# WaterbedSlave.net
KiCad netlist of a schematic drawn in EAGLE
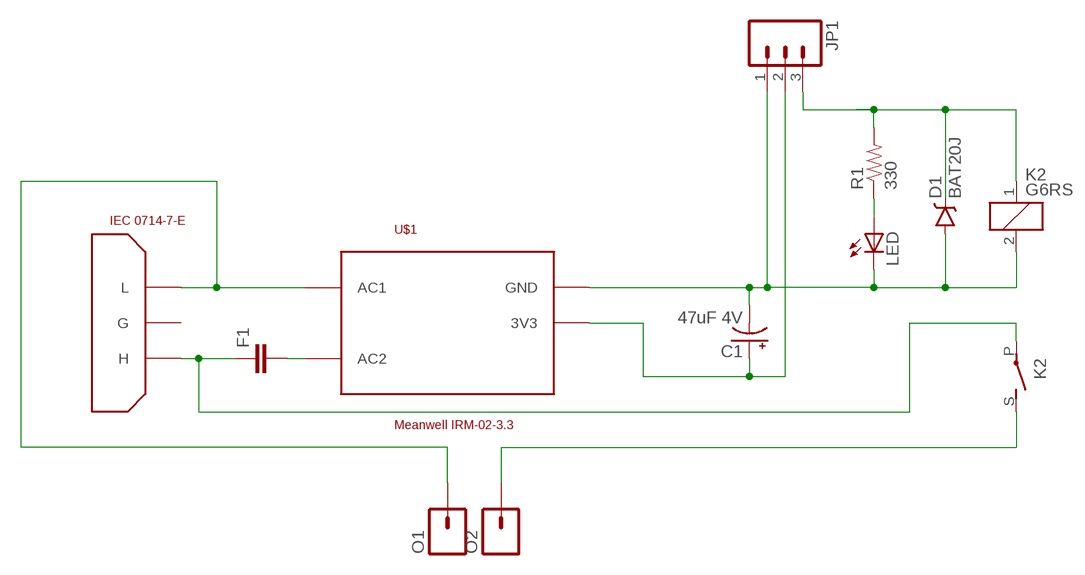
[diagram p0: schematic, sheet 1]

(export (version "E")
  (design (tool "Eeschema 10.0.6"))
  (components
    (comp (ref "C1")
      (value "47uF 4V")
      (footprint "eagle-import:CPOL-RADIAL-10UF-25V")
      (libsource (lib "eagle-import") (part "CAP_POLPTH2"))
    )
    (comp (ref "D1")
      (value "BAT20J")
      (footprint "eagle-import:SOD-323")
      (libsource (lib "eagle-import") (part "DIODE-SCHOTTKY-BAT20J"))
    )
    (comp (ref "F1")
      (value "CAPPTH1")
      (footprint "eagle-import:CAP-PTH-5MM")
      (libsource (lib "eagle-import") (part "CAPPTH1"))
    )
    (comp (ref "JP1")
      (value "M03POLAR_LOCK")
      (footprint "eagle-import:MOLEX-1X3_LOCK")
      (libsource (lib "eagle-import") (part "M03POLAR_LOCK"))
    )
    (comp (ref "K2")
      (value "G6RS")
      (footprint "eagle-import:G6RS")
      (libsource (lib "eagle-import") (part "G6RS"))
    )
    (comp (ref "LED")
      (value "LEDCHIPLED_0805")
      (footprint "eagle-import:CHIPLED_0805")
      (libsource (lib "eagle-import") (part "LEDCHIPLED_0805"))
    )
    (comp (ref "O1")
      (value "M01PTH_2MM")
      (footprint "eagle-import:1X01_2MM")
      (libsource (lib "eagle-import") (part "M01PTH_2MM"))
    )
    (comp (ref "O2")
      (value "M01PTH_2MM")
      (footprint "eagle-import:1X01_2MM")
      (libsource (lib "eagle-import") (part "M01PTH_2MM"))
    )
    (comp (ref "R1")
      (value "330")
      (footprint "eagle-import:0805")
      (libsource (lib "eagle-import") (part "RESISTOR0805-RES"))
    )
    (comp (ref "U$1")
      (value "Meanwell IRM-02-3.3")
      (footprint "eagle-import:RAC02-3.3SC")
      (libsource (lib "eagle-import") (part "RAC02-3.3SC"))
    )
    (comp (ref "U$3")
      (value "IEC 0714-7-E")
      (footprint "eagle-import:IEC")
      (libsource (lib "eagle-import") (part "IEC"))
    )
  )
  (nets
    (net (code "1") (name "Net-(C1-+)") (class "Default")
      (node (ref "C1") (pin "1") (pinfunction "+_1") (pintype "passive"))
      (node (ref "JP1") (pin "2") (pinfunction "2_2") (pintype "passive"))
      (node (ref "U$1") (pin "GND") (pinfunction "3V3_GND") (pintype "bidirectional"))
    )
    (net (code "2") (name "Net-(C1--)") (class "Default")
      (node (ref "C1") (pin "2") (pinfunction "-_2") (pintype "passive"))
      (node (ref "D1") (pin "A") (pinfunction "A_A") (pintype "passive"))
      (node (ref "JP1") (pin "1") (pinfunction "1_1") (pintype "passive"))
      (node (ref "K2") (pin "2") (pinfunction "2_2") (pintype "passive"))
      (node (ref "LED") (pin "C") (pinfunction "C_C") (pintype "passive"))
      (node (ref "U$1") (pin "3V3") (pinfunction "GND_3V3") (pintype "bidirectional"))
    )
    (net (code "3") (name "Net-(D1-PadC)") (class "Default")
      (node (ref "D1") (pin "C") (pinfunction "C_C") (pintype "passive"))
      (node (ref "JP1") (pin "3") (pinfunction "3_3") (pintype "passive"))
      (node (ref "K2") (pin "1") (pinfunction "1_1") (pintype "passive"))
      (node (ref "R1") (pin "2") (pinfunction "2_2") (pintype "passive"))
    )
    (net (code "4") (name "Net-(F1-Pad1)") (class "Default")
      (node (ref "F1") (pin "1") (pinfunction "1_1") (pintype "passive"))
      (node (ref "K2") (pin "P") (pinfunction "P_P") (pintype "passive"))
      (node (ref "U$3") (pin "H") (pinfunction "H_H") (pintype "power_in"))
    )
    (net (code "5") (name "Net-(F1-Pad2)") (class "Default")
      (node (ref "F1") (pin "2") (pinfunction "2_2") (pintype "passive"))
      (node (ref "U$1") (pin "AC2") (pinfunction "AC2_AC2") (pintype "bidirectional"))
    )
    (net (code "6") (name "Net-(K2-PadS)") (class "Default")
      (node (ref "K2") (pin "S") (pinfunction "S_S") (pintype "passive"))
      (node (ref "O2") (pin "1") (pinfunction "1_1") (pintype "passive"))
    )
    (net (code "7") (name "Net-(LED-PadA)") (class "Default")
      (node (ref "LED") (pin "A") (pinfunction "A_A") (pintype "passive"))
      (node (ref "R1") (pin "1") (pinfunction "1_1") (pintype "passive"))
    )
    (net (code "8") (name "Net-(O1-Pad1)") (class "Default")
      (node (ref "O1") (pin "1") (pinfunction "1_1") (pintype "passive"))
      (node (ref "U$1") (pin "AC1") (pinfunction "AC1_AC1") (pintype "bidirectional"))
      (node (ref "U$3") (pin "L") (pinfunction "L_L") (pintype "power_in"))
    )
    (net (code "9") (name "unconnected-(U$3-PadG)") (class "Default")
      (node (ref "U$3") (pin "G") (pinfunction "G_G") (pintype "passive"))
    )
  )
)
